# Connector.net
KiCad netlist of a schematic drawn in Altium Designer
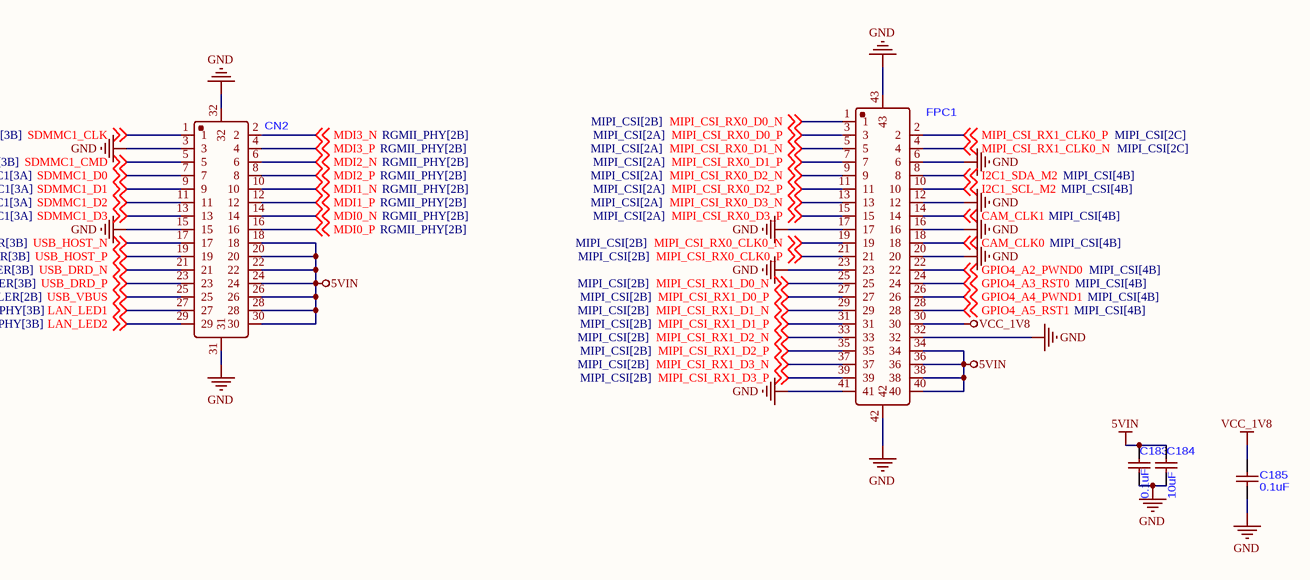
[diagram p0: Connector.SchDoc]

(export (version "E")
  (design (tool "Eeschema 10.0.6"))
  (components
    (comp (ref "C183")
      (value "0.1uF")
      (footprint "C0201")
      (description "0.1uF ±10% 6.3V Ceramic Capacitor X5R 0201")
      (libsource (lib "Schlib1") (part "CAP_100nF-6.3V-10%-0201_1"))
    )
    (comp (ref "C184")
      (value "10uF")
      (footprint "C0402")
      (description "10µF ±20% 10V Ceramic Capacitor X5R 0402 (1005 Metric)")
      (libsource (lib "Schlib1") (part "CAP_10uF-10V-20%-0402"))
    )
    (comp (ref "C185")
      (value "0.1uF")
      (footprint "C0201")
      (description "0.1uF ±10% 6.3V Ceramic Capacitor X5R 0201")
      (libsource (lib "Schlib1") (part "CAP_100nF-6.3V-10%-0201_1"))
    )
    (comp (ref "CN2")
      (value "DF12NB(3.0)-30DP-0.5V(51)")
      (footprint "CONN-SMD_30P-P0.50_HRS_DF12NB-3.0-30DP-0.5V")
      (description "0.5mm Pitch SMT Board-to-Board Connectors, 5Gbps Transmission Speed")
      (libsource (lib "Schlib1") (part "DF12NB(3.0)-30DP-0.5V(51)"))
    )
    (comp (ref "FPC1")
      (value "FH35C-41S-0.3SHW(50)")
      (footprint "FPC-SMD_FH35C-41S-0.3SHW-50")
      (description "CONN FFC FPC 41POS 0.3mm TOP AND BOTTOM CNT SMD R/A")
      (libsource (lib "Schlib1") (part "FH35C-41S-0.3SHW(50)"))
    )
  )
  (nets
    (net (code "1") (name "5VIN") (class "Default")
      (node (ref "C183") (pin "2") (pinfunction "2_2") (pintype "passive"))
      (node (ref "C184") (pin "2") (pinfunction "2_2") (pintype "passive"))
      (node (ref "CN2") (pin "18") (pinfunction "18_18") (pintype "passive"))
      (node (ref "CN2") (pin "20") (pinfunction "20_20") (pintype "passive"))
      (node (ref "CN2") (pin "22") (pinfunction "22_22") (pintype "passive"))
      (node (ref "CN2") (pin "24") (pinfunction "24_24") (pintype "passive"))
      (node (ref "CN2") (pin "26") (pinfunction "26_26") (pintype "passive"))
      (node (ref "CN2") (pin "28") (pinfunction "28_28") (pintype "passive"))
      (node (ref "CN2") (pin "30") (pinfunction "30_30") (pintype "passive"))
      (node (ref "FPC1") (pin "34") (pinfunction "34_34") (pintype "passive"))
      (node (ref "FPC1") (pin "36") (pinfunction "36_36") (pintype "passive"))
      (node (ref "FPC1") (pin "38") (pinfunction "38_38") (pintype "passive"))
      (node (ref "FPC1") (pin "40") (pinfunction "40_40") (pintype "passive"))
    )
    (net (code "2") (name "CAM_CLK0") (class "Default")
      (node (ref "FPC1") (pin "18") (pinfunction "18_18") (pintype "passive"))
    )
    (net (code "3") (name "CAM_CLK1") (class "Default")
      (node (ref "FPC1") (pin "14") (pinfunction "14_14") (pintype "passive"))
    )
    (net (code "4") (name "GND") (class "Default")
      (node (ref "C183") (pin "1") (pinfunction "1_1") (pintype "passive"))
      (node (ref "C184") (pin "1") (pinfunction "1_1") (pintype "passive"))
      (node (ref "C185") (pin "1") (pinfunction "1_1") (pintype "passive"))
      (node (ref "CN2") (pin "15") (pinfunction "15_15") (pintype "passive"))
      (node (ref "CN2") (pin "3") (pinfunction "3_3") (pintype "passive"))
      (node (ref "CN2") (pin "31") (pinfunction "31_31") (pintype "passive"))
      (node (ref "CN2") (pin "32") (pinfunction "32_32") (pintype "passive"))
      (node (ref "FPC1") (pin "12") (pinfunction "12_12") (pintype "passive"))
      (node (ref "FPC1") (pin "16") (pinfunction "16_16") (pintype "passive"))
      (node (ref "FPC1") (pin "17") (pinfunction "17_17") (pintype "passive"))
      (node (ref "FPC1") (pin "20") (pinfunction "20_20") (pintype "passive"))
      (node (ref "FPC1") (pin "23") (pinfunction "23_23") (pintype "passive"))
      (node (ref "FPC1") (pin "32") (pinfunction "32_32") (pintype "passive"))
      (node (ref "FPC1") (pin "41") (pinfunction "41_41") (pintype "passive"))
      (node (ref "FPC1") (pin "42") (pinfunction "42_42") (pintype "passive"))
      (node (ref "FPC1") (pin "43") (pinfunction "43_43") (pintype "passive"))
      (node (ref "FPC1") (pin "6") (pinfunction "6_6") (pintype "passive"))
    )
    (net (code "5") (name "GPIO4_A2_PWND0") (class "Default")
      (node (ref "FPC1") (pin "22") (pinfunction "22_22") (pintype "passive"))
    )
    (net (code "6") (name "GPIO4_A3_RST0") (class "Default")
      (node (ref "FPC1") (pin "24") (pinfunction "24_24") (pintype "passive"))
    )
    (net (code "7") (name "GPIO4_A4_PWND1") (class "Default")
      (node (ref "FPC1") (pin "26") (pinfunction "26_26") (pintype "passive"))
    )
    (net (code "8") (name "GPIO4_A5_RST1") (class "Default")
      (node (ref "FPC1") (pin "28") (pinfunction "28_28") (pintype "passive"))
    )
    (net (code "9") (name "I2C1_SCL_M2") (class "Default")
      (node (ref "FPC1") (pin "10") (pinfunction "10_10") (pintype "passive"))
    )
    (net (code "10") (name "I2C1_SDA_M2") (class "Default")
      (node (ref "FPC1") (pin "8") (pinfunction "8_8") (pintype "passive"))
    )
    (net (code "11") (name "LAN_LED1") (class "Default")
      (node (ref "CN2") (pin "27") (pinfunction "27_27") (pintype "passive"))
    )
    (net (code "12") (name "LAN_LED2") (class "Default")
      (node (ref "CN2") (pin "29") (pinfunction "29_29") (pintype "passive"))
    )
    (net (code "13") (name "MDI0_N") (class "Default")
      (node (ref "CN2") (pin "14") (pinfunction "14_14") (pintype "passive"))
    )
    (net (code "14") (name "MDI0_P") (class "Default")
      (node (ref "CN2") (pin "16") (pinfunction "16_16") (pintype "passive"))
    )
    (net (code "15") (name "MDI1_N") (class "Default")
      (node (ref "CN2") (pin "10") (pinfunction "10_10") (pintype "passive"))
    )
    (net (code "16") (name "MDI1_P") (class "Default")
      (node (ref "CN2") (pin "12") (pinfunction "12_12") (pintype "passive"))
    )
    (net (code "17") (name "MDI2_N") (class "Default")
      (node (ref "CN2") (pin "6") (pinfunction "6_6") (pintype "passive"))
    )
    (net (code "18") (name "MDI2_P") (class "Default")
      (node (ref "CN2") (pin "8") (pinfunction "8_8") (pintype "passive"))
    )
    (net (code "19") (name "MDI3_N") (class "Default")
      (node (ref "CN2") (pin "2") (pinfunction "2_2") (pintype "passive"))
    )
    (net (code "20") (name "MDI3_P") (class "Default")
      (node (ref "CN2") (pin "4") (pinfunction "4_4") (pintype "passive"))
    )
    (net (code "21") (name "MIPI_CSI_RX0_CLK0_N") (class "Default")
      (node (ref "FPC1") (pin "19") (pinfunction "19_19") (pintype "passive"))
    )
    (net (code "22") (name "MIPI_CSI_RX0_CLK0_P") (class "Default")
      (node (ref "FPC1") (pin "21") (pinfunction "21_21") (pintype "passive"))
    )
    (net (code "23") (name "MIPI_CSI_RX0_D0_N") (class "Default")
      (node (ref "FPC1") (pin "1") (pinfunction "1_1") (pintype "passive"))
    )
    (net (code "24") (name "MIPI_CSI_RX0_D0_P") (class "Default")
      (node (ref "FPC1") (pin "3") (pinfunction "3_3") (pintype "passive"))
    )
    (net (code "25") (name "MIPI_CSI_RX0_D1_N") (class "Default")
      (node (ref "FPC1") (pin "5") (pinfunction "5_5") (pintype "passive"))
    )
    (net (code "26") (name "MIPI_CSI_RX0_D1_P") (class "Default")
      (node (ref "FPC1") (pin "7") (pinfunction "7_7") (pintype "passive"))
    )
    (net (code "27") (name "MIPI_CSI_RX0_D2_N") (class "Default")
      (node (ref "FPC1") (pin "9") (pinfunction "9_9") (pintype "passive"))
    )
    (net (code "28") (name "MIPI_CSI_RX0_D2_P") (class "Default")
      (node (ref "FPC1") (pin "11") (pinfunction "11_11") (pintype "passive"))
    )
    (net (code "29") (name "MIPI_CSI_RX0_D3_N") (class "Default")
      (node (ref "FPC1") (pin "13") (pinfunction "13_13") (pintype "passive"))
    )
    (net (code "30") (name "MIPI_CSI_RX0_D3_P") (class "Default")
      (node (ref "FPC1") (pin "15") (pinfunction "15_15") (pintype "passive"))
    )
    (net (code "31") (name "MIPI_CSI_RX1_CLK0_N") (class "Default")
      (node (ref "FPC1") (pin "4") (pinfunction "4_4") (pintype "passive"))
    )
    (net (code "32") (name "MIPI_CSI_RX1_CLK0_P") (class "Default")
      (node (ref "FPC1") (pin "2") (pinfunction "2_2") (pintype "passive"))
    )
    (net (code "33") (name "MIPI_CSI_RX1_D0_N") (class "Default")
      (node (ref "FPC1") (pin "25") (pinfunction "25_25") (pintype "passive"))
    )
    (net (code "34") (name "MIPI_CSI_RX1_D0_P") (class "Default")
      (node (ref "FPC1") (pin "27") (pinfunction "27_27") (pintype "passive"))
    )
    (net (code "35") (name "MIPI_CSI_RX1_D1_N") (class "Default")
      (node (ref "FPC1") (pin "29") (pinfunction "29_29") (pintype "passive"))
    )
    (net (code "36") (name "MIPI_CSI_RX1_D1_P") (class "Default")
      (node (ref "FPC1") (pin "31") (pinfunction "31_31") (pintype "passive"))
    )
    (net (code "37") (name "MIPI_CSI_RX1_D2_N") (class "Default")
      (node (ref "FPC1") (pin "33") (pinfunction "33_33") (pintype "passive"))
    )
    (net (code "38") (name "MIPI_CSI_RX1_D2_P") (class "Default")
      (node (ref "FPC1") (pin "35") (pinfunction "35_35") (pintype "passive"))
    )
    (net (code "39") (name "MIPI_CSI_RX1_D3_N") (class "Default")
      (node (ref "FPC1") (pin "37") (pinfunction "37_37") (pintype "passive"))
    )
    (net (code "40") (name "MIPI_CSI_RX1_D3_P") (class "Default")
      (node (ref "FPC1") (pin "39") (pinfunction "39_39") (pintype "passive"))
    )
    (net (code "41") (name "SDMMC1_CLK") (class "Default")
      (node (ref "CN2") (pin "1") (pinfunction "1_1") (pintype "passive"))
    )
    (net (code "42") (name "SDMMC1_CMD") (class "Default")
      (node (ref "CN2") (pin "5") (pinfunction "5_5") (pintype "passive"))
    )
    (net (code "43") (name "SDMMC1_D0") (class "Default")
      (node (ref "CN2") (pin "7") (pinfunction "7_7") (pintype "passive"))
    )
    (net (code "44") (name "SDMMC1_D1") (class "Default")
      (node (ref "CN2") (pin "9") (pinfunction "9_9") (pintype "passive"))
    )
    (net (code "45") (name "SDMMC1_D2") (class "Default")
      (node (ref "CN2") (pin "11") (pinfunction "11_11") (pintype "passive"))
    )
    (net (code "46") (name "SDMMC1_D3") (class "Default")
      (node (ref "CN2") (pin "13") (pinfunction "13_13") (pintype "passive"))
    )
    (net (code "47") (name "USB_DRD_N") (class "Default")
      (node (ref "CN2") (pin "21") (pinfunction "21_21") (pintype "passive"))
    )
    (net (code "48") (name "USB_DRD_P") (class "Default")
      (node (ref "CN2") (pin "23") (pinfunction "23_23") (pintype "passive"))
    )
    (net (code "49") (name "USB_HOST_N") (class "Default")
      (node (ref "CN2") (pin "17") (pinfunction "17_17") (pintype "passive"))
    )
    (net (code "50") (name "USB_HOST_P") (class "Default")
      (node (ref "CN2") (pin "19") (pinfunction "19_19") (pintype "passive"))
    )
    (net (code "51") (name "USB_VBUS") (class "Default")
      (node (ref "CN2") (pin "25") (pinfunction "25_25") (pintype "passive"))
    )
    (net (code "52") (name "VCC_1V8") (class "Default")
      (node (ref "C185") (pin "2") (pinfunction "2_2") (pintype "passive"))
      (node (ref "FPC1") (pin "30") (pinfunction "30_30") (pintype "passive"))
    )
  )
)
